# Hi-Hat_copy.net
KiCad netlist of a schematic drawn in EAGLE
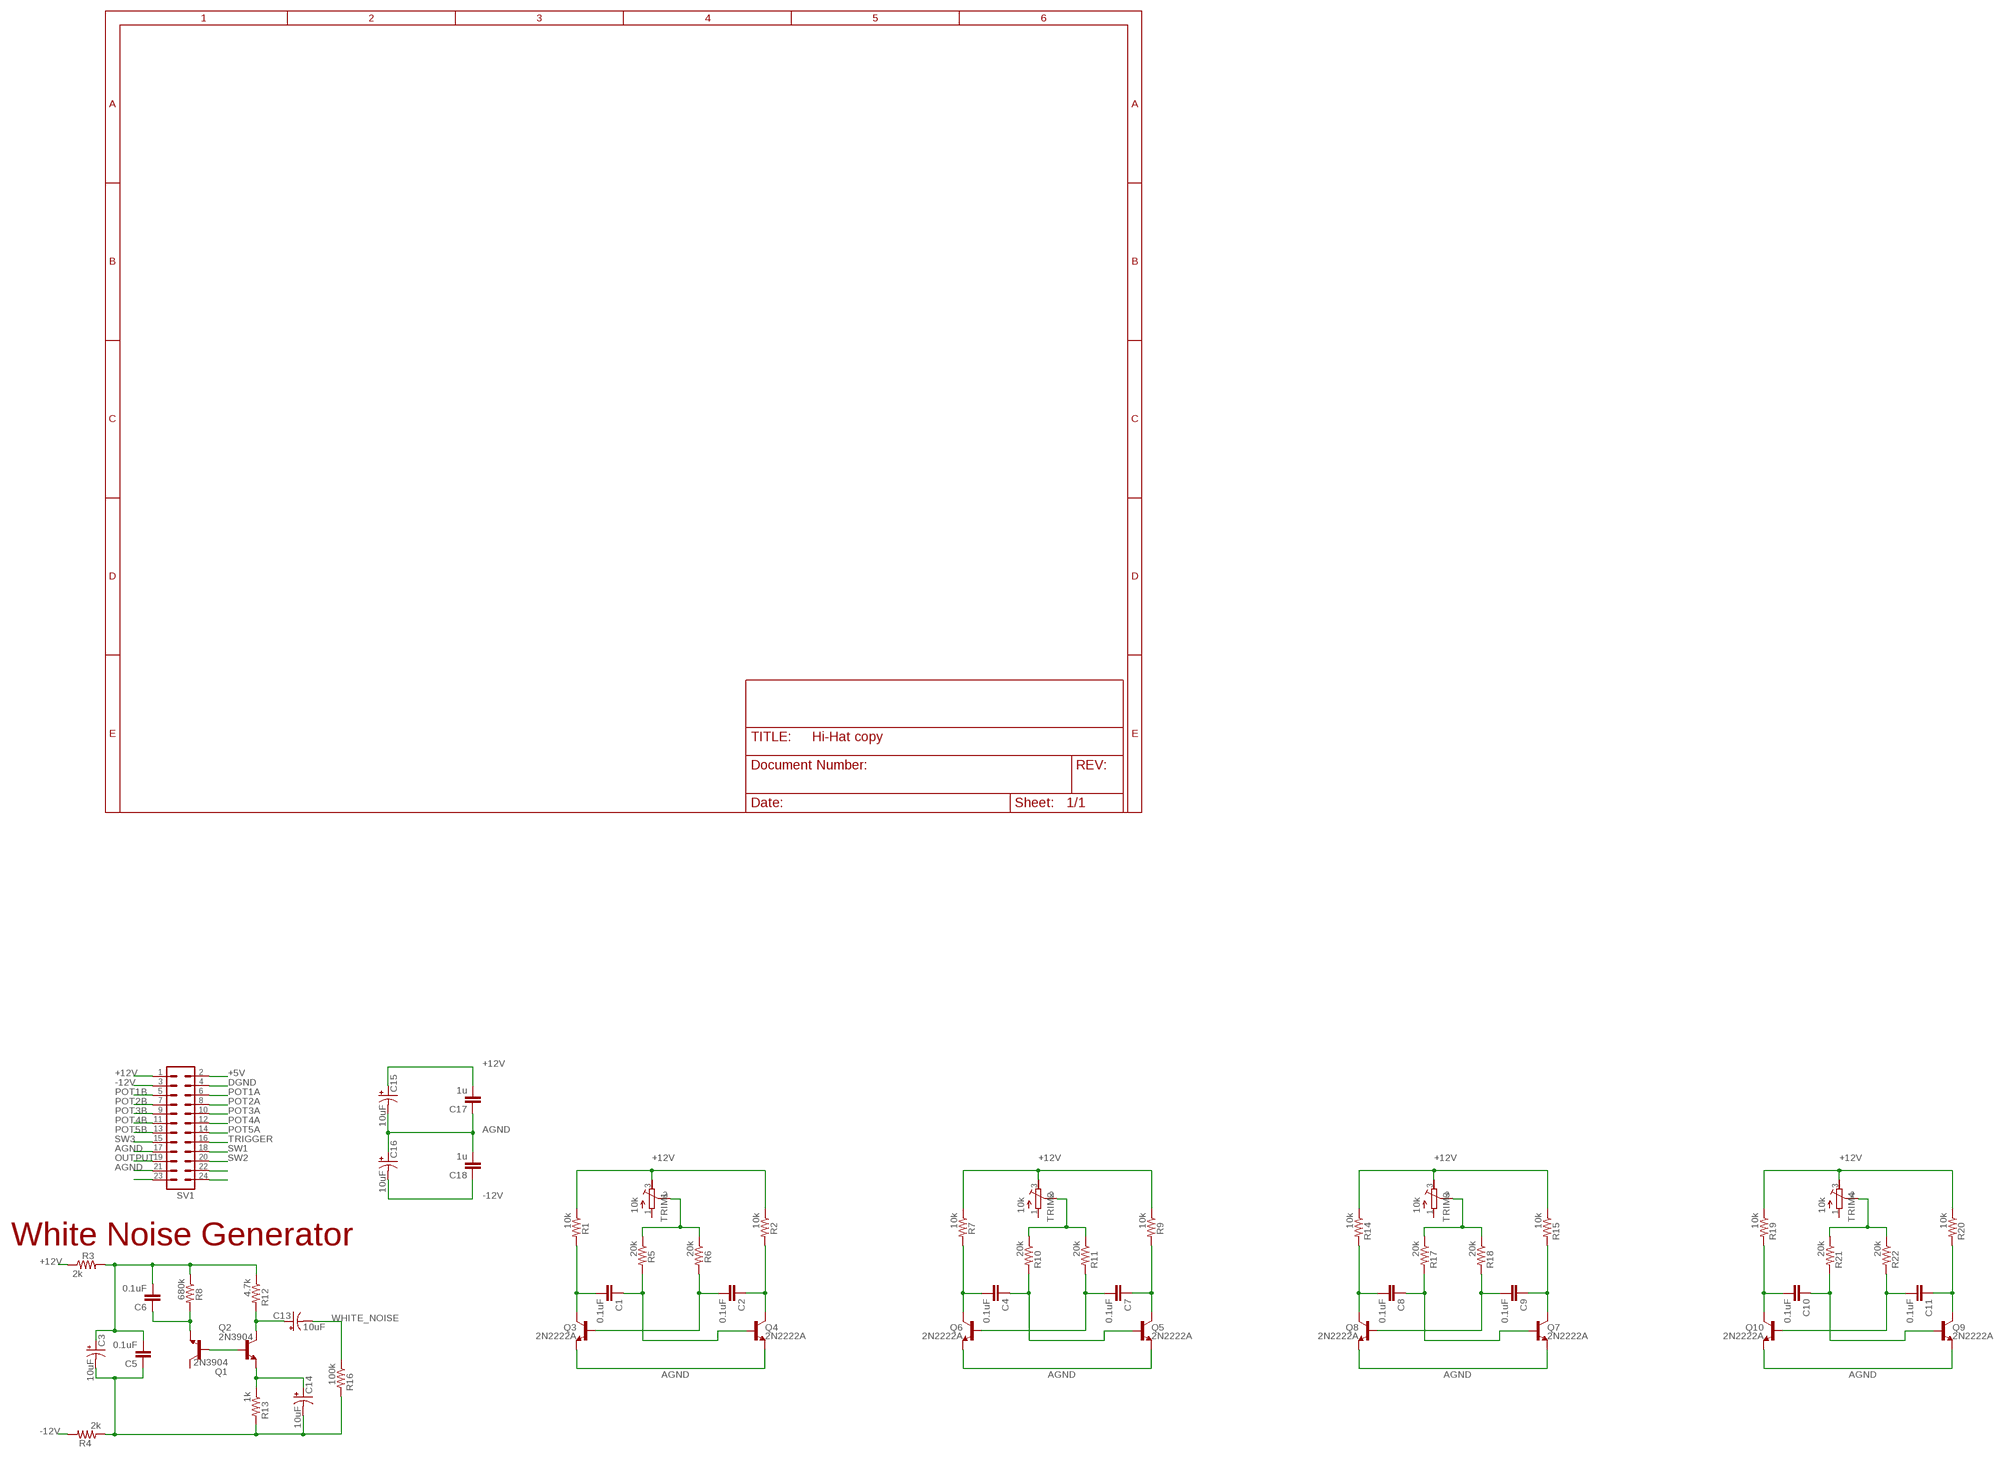
[diagram p0: schematic, sheet 1]

(export (version "E")
  (design (tool "Eeschema 10.0.6"))
  (components
    (comp (ref "C1")
      (value "0.1uF")
      (footprint "eagle-import:C050-024X044")
      (libsource (lib "eagle-import") (part "C-EU050-024X044"))
    )
    (comp (ref "C2")
      (value "0.1uF")
      (footprint "eagle-import:C050-024X044")
      (libsource (lib "eagle-import") (part "C-EU050-024X044"))
    )
    (comp (ref "C3")
      (value "10uF")
      (footprint "eagle-import:E2,5-6")
      (libsource (lib "eagle-import") (part "CPOL-USE2.5-6"))
    )
    (comp (ref "C4")
      (value "0.1uF")
      (footprint "eagle-import:C050-024X044")
      (libsource (lib "eagle-import") (part "C-EU050-024X044"))
    )
    (comp (ref "C5")
      (value "0.1uF")
      (footprint "eagle-import:C050-024X044")
      (libsource (lib "eagle-import") (part "C-EU050-024X044"))
    )
    (comp (ref "C6")
      (value "0.1uF")
      (footprint "eagle-import:C050-024X044")
      (libsource (lib "eagle-import") (part "C-EU050-024X044"))
    )
    (comp (ref "C7")
      (value "0.1uF")
      (footprint "eagle-import:C050-024X044")
      (libsource (lib "eagle-import") (part "C-EU050-024X044"))
    )
    (comp (ref "C8")
      (value "0.1uF")
      (footprint "eagle-import:C050-024X044")
      (libsource (lib "eagle-import") (part "C-EU050-024X044"))
    )
    (comp (ref "C9")
      (value "0.1uF")
      (footprint "eagle-import:C050-024X044")
      (libsource (lib "eagle-import") (part "C-EU050-024X044"))
    )
    (comp (ref "C10")
      (value "0.1uF")
      (footprint "eagle-import:C050-024X044")
      (libsource (lib "eagle-import") (part "C-EU050-024X044"))
    )
    (comp (ref "C11")
      (value "0.1uF")
      (footprint "eagle-import:C050-024X044")
      (libsource (lib "eagle-import") (part "C-EU050-024X044"))
    )
    (comp (ref "C13")
      (value "10uF")
      (footprint "eagle-import:E2,5-6")
      (libsource (lib "eagle-import") (part "CPOL-USE2.5-6"))
    )
    (comp (ref "C14")
      (value "10uF")
      (footprint "eagle-import:E2,5-6")
      (libsource (lib "eagle-import") (part "CPOL-USE2.5-6"))
    )
    (comp (ref "C15")
      (value "10uF")
      (footprint "eagle-import:E2,5-6")
      (libsource (lib "eagle-import") (part "CPOL-USE2.5-6"))
    )
    (comp (ref "C16")
      (value "10uF")
      (footprint "eagle-import:E2,5-6")
      (libsource (lib "eagle-import") (part "CPOL-USE2.5-6"))
    )
    (comp (ref "C17")
      (value "1u")
      (footprint "eagle-import:C050-024X044")
      (libsource (lib "eagle-import") (part "C-EU050-024X044"))
    )
    (comp (ref "C18")
      (value "1u")
      (footprint "eagle-import:C050-024X044")
      (libsource (lib "eagle-import") (part "C-EU050-024X044"))
    )
    (comp (ref "Q1")
      (value "2N3904")
      (footprint "eagle-import:TO92")
      (libsource (lib "eagle-import") (part "2N3904"))
    )
    (comp (ref "Q2")
      (value "2N3904")
      (footprint "eagle-import:TO92")
      (libsource (lib "eagle-import") (part "2N3904"))
    )
    (comp (ref "Q3")
      (value "2N2222A")
      (footprint "eagle-import:TO-92")
      (libsource (lib "eagle-import") (part "TRANS_NPN-P2N2222A"))
    )
    (comp (ref "Q4")
      (value "2N2222A")
      (footprint "eagle-import:TO-92")
      (libsource (lib "eagle-import") (part "TRANS_NPN-P2N2222A"))
    )
    (comp (ref "Q5")
      (value "2N2222A")
      (footprint "eagle-import:TO-92")
      (libsource (lib "eagle-import") (part "TRANS_NPN-P2N2222A"))
    )
    (comp (ref "Q6")
      (value "2N2222A")
      (footprint "eagle-import:TO-92")
      (libsource (lib "eagle-import") (part "TRANS_NPN-P2N2222A"))
    )
    (comp (ref "Q7")
      (value "2N2222A")
      (footprint "eagle-import:TO-92")
      (libsource (lib "eagle-import") (part "TRANS_NPN-P2N2222A"))
    )
    (comp (ref "Q8")
      (value "2N2222A")
      (footprint "eagle-import:TO-92")
      (libsource (lib "eagle-import") (part "TRANS_NPN-P2N2222A"))
    )
    (comp (ref "Q9")
      (value "2N2222A")
      (footprint "eagle-import:TO-92")
      (libsource (lib "eagle-import") (part "TRANS_NPN-P2N2222A"))
    )
    (comp (ref "Q10")
      (value "2N2222A")
      (footprint "eagle-import:TO-92")
      (libsource (lib "eagle-import") (part "TRANS_NPN-P2N2222A"))
    )
    (comp (ref "R1")
      (value "10k")
      (footprint "eagle-import:0207_10")
      (libsource (lib "eagle-import") (part "R-US_0207/10"))
    )
    (comp (ref "R2")
      (value "10k")
      (footprint "eagle-import:0207_10")
      (libsource (lib "eagle-import") (part "R-US_0207/10"))
    )
    (comp (ref "R3")
      (value "2k")
      (footprint "eagle-import:0207_10")
      (libsource (lib "eagle-import") (part "R-US_0207/10"))
    )
    (comp (ref "R4")
      (value "2k")
      (footprint "eagle-import:0207_10")
      (libsource (lib "eagle-import") (part "R-US_0207/10"))
    )
    (comp (ref "R5")
      (value "20k")
      (footprint "eagle-import:0207_10")
      (libsource (lib "eagle-import") (part "R-US_0207/10"))
    )
    (comp (ref "R6")
      (value "20k")
      (footprint "eagle-import:0207_10")
      (libsource (lib "eagle-import") (part "R-US_0207/10"))
    )
    (comp (ref "R7")
      (value "10k")
      (footprint "eagle-import:0207_10")
      (libsource (lib "eagle-import") (part "R-US_0207/10"))
    )
    (comp (ref "R8")
      (value "680k")
      (footprint "eagle-import:0207_10")
      (libsource (lib "eagle-import") (part "R-US_0207/10"))
    )
    (comp (ref "R9")
      (value "10k")
      (footprint "eagle-import:0207_10")
      (libsource (lib "eagle-import") (part "R-US_0207/10"))
    )
    (comp (ref "R10")
      (value "20k")
      (footprint "eagle-import:0207_10")
      (libsource (lib "eagle-import") (part "R-US_0207/10"))
    )
    (comp (ref "R11")
      (value "20k")
      (footprint "eagle-import:0207_10")
      (libsource (lib "eagle-import") (part "R-US_0207/10"))
    )
    (comp (ref "R12")
      (value "4.7k")
      (footprint "eagle-import:0207_10")
      (libsource (lib "eagle-import") (part "R-US_0207/10"))
    )
    (comp (ref "R13")
      (value "1k")
      (footprint "eagle-import:0207_10")
      (libsource (lib "eagle-import") (part "R-US_0207/10"))
    )
    (comp (ref "R14")
      (value "10k")
      (footprint "eagle-import:0207_10")
      (libsource (lib "eagle-import") (part "R-US_0207/10"))
    )
    (comp (ref "R15")
      (value "10k")
      (footprint "eagle-import:0207_10")
      (libsource (lib "eagle-import") (part "R-US_0207/10"))
    )
    (comp (ref "R16")
      (value "100k")
      (footprint "eagle-import:0207_10")
      (libsource (lib "eagle-import") (part "R-US_0207/10"))
    )
    (comp (ref "R17")
      (value "20k")
      (footprint "eagle-import:0207_10")
      (libsource (lib "eagle-import") (part "R-US_0207/10"))
    )
    (comp (ref "R18")
      (value "20k")
      (footprint "eagle-import:0207_10")
      (libsource (lib "eagle-import") (part "R-US_0207/10"))
    )
    (comp (ref "R19")
      (value "10k")
      (footprint "eagle-import:0207_10")
      (libsource (lib "eagle-import") (part "R-US_0207/10"))
    )
    (comp (ref "R20")
      (value "10k")
      (footprint "eagle-import:0207_10")
      (libsource (lib "eagle-import") (part "R-US_0207/10"))
    )
    (comp (ref "R21")
      (value "20k")
      (footprint "eagle-import:0207_10")
      (libsource (lib "eagle-import") (part "R-US_0207/10"))
    )
    (comp (ref "R22")
      (value "20k")
      (footprint "eagle-import:0207_10")
      (libsource (lib "eagle-import") (part "R-US_0207/10"))
    )
    (comp (ref "SV1")
      (value "MA12-2")
      (footprint "eagle-import:MA12-2")
      (libsource (lib "eagle-import") (part "MA12-2"))
    )
    (comp (ref "TRIM1")
      (value "10k")
      (footprint "eagle-import:RTRIM64W")
      (libsource (lib "eagle-import") (part "R-TRIMM64W"))
    )
    (comp (ref "TRIM2")
      (value "10k")
      (footprint "eagle-import:RTRIM64W")
      (libsource (lib "eagle-import") (part "R-TRIMM64W"))
    )
    (comp (ref "TRIM3")
      (value "10k")
      (footprint "eagle-import:RTRIM64W")
      (libsource (lib "eagle-import") (part "R-TRIMM64W"))
    )
    (comp (ref "TRIM4")
      (value "10k")
      (footprint "eagle-import:RTRIM64W")
      (libsource (lib "eagle-import") (part "R-TRIMM64W"))
    )
  )
  (nets
    (net (code "1") (name "/+5V") (class "Default")
      (node (ref "SV1") (pin "2") (pinfunction "2_2") (pintype "passive"))
    )
    (net (code "2") (name "/+12V") (class "Default")
      (node (ref "C15") (pin "+") (pinfunction "+_+") (pintype "passive"))
      (node (ref "C17") (pin "2") (pinfunction "2_2") (pintype "passive"))
      (node (ref "R1") (pin "1") (pinfunction "1_1") (pintype "passive"))
      (node (ref "R14") (pin "1") (pinfunction "1_1") (pintype "passive"))
      (node (ref "R15") (pin "1") (pinfunction "1_1") (pintype "passive"))
      (node (ref "R19") (pin "1") (pinfunction "1_1") (pintype "passive"))
      (node (ref "R2") (pin "1") (pinfunction "1_1") (pintype "passive"))
      (node (ref "R20") (pin "1") (pinfunction "1_1") (pintype "passive"))
      (node (ref "R3") (pin "1") (pinfunction "1_1") (pintype "passive"))
      (node (ref "R7") (pin "1") (pinfunction "1_1") (pintype "passive"))
      (node (ref "R9") (pin "1") (pinfunction "1_1") (pintype "passive"))
      (node (ref "SV1") (pin "1") (pinfunction "1_1") (pintype "passive"))
      (node (ref "TRIM1") (pin "3") (pinfunction "E_3") (pintype "passive"))
      (node (ref "TRIM2") (pin "3") (pinfunction "E_3") (pintype "passive"))
      (node (ref "TRIM3") (pin "3") (pinfunction "E_3") (pintype "passive"))
      (node (ref "TRIM4") (pin "3") (pinfunction "E_3") (pintype "passive"))
    )
    (net (code "3") (name "/-12V") (class "Default")
      (node (ref "C16") (pin "-") (pinfunction "-_-") (pintype "passive"))
      (node (ref "C18") (pin "1") (pinfunction "1_1") (pintype "passive"))
      (node (ref "R4") (pin "2") (pinfunction "2_2") (pintype "passive"))
      (node (ref "SV1") (pin "3") (pinfunction "3_3") (pintype "passive"))
    )
    (net (code "4") (name "/AGND") (class "Default")
      (node (ref "C15") (pin "-") (pinfunction "-_-") (pintype "passive"))
      (node (ref "C16") (pin "+") (pinfunction "+_+") (pintype "passive"))
      (node (ref "C17") (pin "1") (pinfunction "1_1") (pintype "passive"))
      (node (ref "C18") (pin "2") (pinfunction "2_2") (pintype "passive"))
      (node (ref "Q10") (pin "3") (pinfunction "E_3") (pintype "passive"))
      (node (ref "Q3") (pin "3") (pinfunction "E_3") (pintype "passive"))
      (node (ref "Q4") (pin "3") (pinfunction "E_3") (pintype "passive"))
      (node (ref "Q5") (pin "3") (pinfunction "E_3") (pintype "passive"))
      (node (ref "Q6") (pin "3") (pinfunction "E_3") (pintype "passive"))
      (node (ref "Q7") (pin "3") (pinfunction "E_3") (pintype "passive"))
      (node (ref "Q8") (pin "3") (pinfunction "E_3") (pintype "passive"))
      (node (ref "Q9") (pin "3") (pinfunction "E_3") (pintype "passive"))
      (node (ref "SV1") (pin "17") (pinfunction "17_17") (pintype "passive"))
      (node (ref "SV1") (pin "21") (pinfunction "21_21") (pintype "passive"))
    )
    (net (code "5") (name "/DGND") (class "Default")
      (node (ref "SV1") (pin "4") (pinfunction "4_4") (pintype "passive"))
    )
    (net (code "6") (name "/OUTPUT") (class "Default")
      (node (ref "SV1") (pin "19") (pinfunction "19_19") (pintype "passive"))
    )
    (net (code "7") (name "/POT1A") (class "Default")
      (node (ref "SV1") (pin "6") (pinfunction "6_6") (pintype "passive"))
    )
    (net (code "8") (name "/POT1B") (class "Default")
      (node (ref "SV1") (pin "5") (pinfunction "5_5") (pintype "passive"))
    )
    (net (code "9") (name "/POT2A") (class "Default")
      (node (ref "SV1") (pin "8") (pinfunction "8_8") (pintype "passive"))
    )
    (net (code "10") (name "/POT2B") (class "Default")
      (node (ref "SV1") (pin "7") (pinfunction "7_7") (pintype "passive"))
    )
    (net (code "11") (name "/POT3A") (class "Default")
      (node (ref "SV1") (pin "10") (pinfunction "10_10") (pintype "passive"))
    )
    (net (code "12") (name "/POT3B") (class "Default")
      (node (ref "SV1") (pin "9") (pinfunction "9_9") (pintype "passive"))
    )
    (net (code "13") (name "/POT4A") (class "Default")
      (node (ref "SV1") (pin "12") (pinfunction "12_12") (pintype "passive"))
    )
    (net (code "14") (name "/POT4B") (class "Default")
      (node (ref "SV1") (pin "11") (pinfunction "11_11") (pintype "passive"))
    )
    (net (code "15") (name "/POT5A") (class "Default")
      (node (ref "SV1") (pin "14") (pinfunction "14_14") (pintype "passive"))
    )
    (net (code "16") (name "/POT5B") (class "Default")
      (node (ref "SV1") (pin "13") (pinfunction "13_13") (pintype "passive"))
    )
    (net (code "17") (name "/SW1") (class "Default")
      (node (ref "SV1") (pin "18") (pinfunction "18_18") (pintype "passive"))
    )
    (net (code "18") (name "/SW2") (class "Default")
      (node (ref "SV1") (pin "20") (pinfunction "20_20") (pintype "passive"))
    )
    (net (code "19") (name "/SW3") (class "Default")
      (node (ref "SV1") (pin "15") (pinfunction "15_15") (pintype "passive"))
    )
    (net (code "20") (name "/TRIGGER") (class "Default")
      (node (ref "SV1") (pin "16") (pinfunction "16_16") (pintype "passive"))
    )
    (net (code "21") (name "/WHITE_NOISE") (class "Default")
      (node (ref "C13") (pin "-") (pinfunction "-_-") (pintype "passive"))
      (node (ref "R16") (pin "1") (pinfunction "1_1") (pintype "passive"))
    )
    (net (code "22") (name "Net-(C3-Pad+)") (class "Default")
      (node (ref "C3") (pin "+") (pinfunction "+_+") (pintype "passive"))
      (node (ref "C5") (pin "2") (pinfunction "2_2") (pintype "passive"))
      (node (ref "C6") (pin "2") (pinfunction "2_2") (pintype "passive"))
      (node (ref "R12") (pin "1") (pinfunction "1_1") (pintype "passive"))
      (node (ref "R3") (pin "2") (pinfunction "2_2") (pintype "passive"))
      (node (ref "R8") (pin "1") (pinfunction "1_1") (pintype "passive"))
    )
    (net (code "23") (name "Net-(C14-Pad-)") (class "Default")
      (node (ref "C14") (pin "-") (pinfunction "-_-") (pintype "passive"))
      (node (ref "C3") (pin "-") (pinfunction "-_-") (pintype "passive"))
      (node (ref "C5") (pin "1") (pinfunction "1_1") (pintype "passive"))
      (node (ref "R13") (pin "2") (pinfunction "2_2") (pintype "passive"))
      (node (ref "R16") (pin "2") (pinfunction "2_2") (pintype "passive"))
      (node (ref "R4") (pin "1") (pinfunction "1_1") (pintype "passive"))
    )
    (net (code "24") (name "Net-(Q1-B)") (class "Default")
      (node (ref "Q1") (pin "2") (pinfunction "B_2") (pintype "passive"))
      (node (ref "Q2") (pin "2") (pinfunction "B_2") (pintype "passive"))
    )
    (net (code "25") (name "Net-(Q1-E)") (class "Default")
      (node (ref "C6") (pin "1") (pinfunction "1_1") (pintype "passive"))
      (node (ref "Q1") (pin "3") (pinfunction "E_3") (pintype "passive"))
      (node (ref "R8") (pin "2") (pinfunction "2_2") (pintype "passive"))
    )
    (net (code "26") (name "Net-(Q2-C)") (class "Default")
      (node (ref "C13") (pin "+") (pinfunction "+_+") (pintype "passive"))
      (node (ref "Q2") (pin "1") (pinfunction "C_1") (pintype "passive"))
      (node (ref "R12") (pin "2") (pinfunction "2_2") (pintype "passive"))
    )
    (net (code "27") (name "Net-(Q2-E)") (class "Default")
      (node (ref "C14") (pin "+") (pinfunction "+_+") (pintype "passive"))
      (node (ref "Q2") (pin "3") (pinfunction "E_3") (pintype "passive"))
      (node (ref "R13") (pin "1") (pinfunction "1_1") (pintype "passive"))
    )
    (net (code "28") (name "Net-(Q3-B)") (class "Default")
      (node (ref "C2") (pin "2") (pinfunction "2_2") (pintype "passive"))
      (node (ref "Q3") (pin "2") (pinfunction "B_2") (pintype "passive"))
      (node (ref "R6") (pin "2") (pinfunction "2_2") (pintype "passive"))
    )
    (net (code "29") (name "Net-(Q3-C)") (class "Default")
      (node (ref "C1") (pin "2") (pinfunction "2_2") (pintype "passive"))
      (node (ref "Q3") (pin "1") (pinfunction "C_1") (pintype "passive"))
      (node (ref "R1") (pin "2") (pinfunction "2_2") (pintype "passive"))
    )
    (net (code "30") (name "Net-(Q4-B)") (class "Default")
      (node (ref "C1") (pin "1") (pinfunction "1_1") (pintype "passive"))
      (node (ref "Q4") (pin "2") (pinfunction "B_2") (pintype "passive"))
      (node (ref "R5") (pin "2") (pinfunction "2_2") (pintype "passive"))
    )
    (net (code "31") (name "Net-(Q4-C)") (class "Default")
      (node (ref "C2") (pin "1") (pinfunction "1_1") (pintype "passive"))
      (node (ref "Q4") (pin "1") (pinfunction "C_1") (pintype "passive"))
      (node (ref "R2") (pin "2") (pinfunction "2_2") (pintype "passive"))
    )
    (net (code "32") (name "Net-(Q5-B)") (class "Default")
      (node (ref "C4") (pin "1") (pinfunction "1_1") (pintype "passive"))
      (node (ref "Q5") (pin "2") (pinfunction "B_2") (pintype "passive"))
      (node (ref "R10") (pin "2") (pinfunction "2_2") (pintype "passive"))
    )
    (net (code "33") (name "Net-(Q5-C)") (class "Default")
      (node (ref "C7") (pin "1") (pinfunction "1_1") (pintype "passive"))
      (node (ref "Q5") (pin "1") (pinfunction "C_1") (pintype "passive"))
      (node (ref "R9") (pin "2") (pinfunction "2_2") (pintype "passive"))
    )
    (net (code "34") (name "Net-(Q6-B)") (class "Default")
      (node (ref "C7") (pin "2") (pinfunction "2_2") (pintype "passive"))
      (node (ref "Q6") (pin "2") (pinfunction "B_2") (pintype "passive"))
      (node (ref "R11") (pin "2") (pinfunction "2_2") (pintype "passive"))
    )
    (net (code "35") (name "Net-(Q6-C)") (class "Default")
      (node (ref "C4") (pin "2") (pinfunction "2_2") (pintype "passive"))
      (node (ref "Q6") (pin "1") (pinfunction "C_1") (pintype "passive"))
      (node (ref "R7") (pin "2") (pinfunction "2_2") (pintype "passive"))
    )
    (net (code "36") (name "Net-(Q7-B)") (class "Default")
      (node (ref "C8") (pin "1") (pinfunction "1_1") (pintype "passive"))
      (node (ref "Q7") (pin "2") (pinfunction "B_2") (pintype "passive"))
      (node (ref "R17") (pin "2") (pinfunction "2_2") (pintype "passive"))
    )
    (net (code "37") (name "Net-(Q7-C)") (class "Default")
      (node (ref "C9") (pin "1") (pinfunction "1_1") (pintype "passive"))
      (node (ref "Q7") (pin "1") (pinfunction "C_1") (pintype "passive"))
      (node (ref "R15") (pin "2") (pinfunction "2_2") (pintype "passive"))
    )
    (net (code "38") (name "Net-(Q8-B)") (class "Default")
      (node (ref "C9") (pin "2") (pinfunction "2_2") (pintype "passive"))
      (node (ref "Q8") (pin "2") (pinfunction "B_2") (pintype "passive"))
      (node (ref "R18") (pin "2") (pinfunction "2_2") (pintype "passive"))
    )
    (net (code "39") (name "Net-(Q8-C)") (class "Default")
      (node (ref "C8") (pin "2") (pinfunction "2_2") (pintype "passive"))
      (node (ref "Q8") (pin "1") (pinfunction "C_1") (pintype "passive"))
      (node (ref "R14") (pin "2") (pinfunction "2_2") (pintype "passive"))
    )
    (net (code "40") (name "Net-(Q9-B)") (class "Default")
      (node (ref "C10") (pin "1") (pinfunction "1_1") (pintype "passive"))
      (node (ref "Q9") (pin "2") (pinfunction "B_2") (pintype "passive"))
      (node (ref "R21") (pin "2") (pinfunction "2_2") (pintype "passive"))
    )
    (net (code "41") (name "Net-(Q9-C)") (class "Default")
      (node (ref "C11") (pin "1") (pinfunction "1_1") (pintype "passive"))
      (node (ref "Q9") (pin "1") (pinfunction "C_1") (pintype "passive"))
      (node (ref "R20") (pin "2") (pinfunction "2_2") (pintype "passive"))
    )
    (net (code "42") (name "Net-(Q10-B)") (class "Default")
      (node (ref "C11") (pin "2") (pinfunction "2_2") (pintype "passive"))
      (node (ref "Q10") (pin "2") (pinfunction "B_2") (pintype "passive"))
      (node (ref "R22") (pin "2") (pinfunction "2_2") (pintype "passive"))
    )
    (net (code "43") (name "Net-(Q10-C)") (class "Default")
      (node (ref "C10") (pin "2") (pinfunction "2_2") (pintype "passive"))
      (node (ref "Q10") (pin "1") (pinfunction "C_1") (pintype "passive"))
      (node (ref "R19") (pin "2") (pinfunction "2_2") (pintype "passive"))
    )
    (net (code "44") (name "Net-(TRIM1-S)") (class "Default")
      (node (ref "R5") (pin "1") (pinfunction "1_1") (pintype "passive"))
      (node (ref "R6") (pin "1") (pinfunction "1_1") (pintype "passive"))
      (node (ref "TRIM1") (pin "2") (pinfunction "S_2") (pintype "passive"))
    )
    (net (code "45") (name "Net-(TRIM2-S)") (class "Default")
      (node (ref "R10") (pin "1") (pinfunction "1_1") (pintype "passive"))
      (node (ref "R11") (pin "1") (pinfunction "1_1") (pintype "passive"))
      (node (ref "TRIM2") (pin "2") (pinfunction "S_2") (pintype "passive"))
    )
    (net (code "46") (name "Net-(TRIM3-S)") (class "Default")
      (node (ref "R17") (pin "1") (pinfunction "1_1") (pintype "passive"))
      (node (ref "R18") (pin "1") (pinfunction "1_1") (pintype "passive"))
      (node (ref "TRIM3") (pin "2") (pinfunction "S_2") (pintype "passive"))
    )
    (net (code "47") (name "Net-(TRIM4-S)") (class "Default")
      (node (ref "R21") (pin "1") (pinfunction "1_1") (pintype "passive"))
      (node (ref "R22") (pin "1") (pinfunction "1_1") (pintype "passive"))
      (node (ref "TRIM4") (pin "2") (pinfunction "S_2") (pintype "passive"))
    )
    (net (code "48") (name "unconnected-(Q1-C-Pad1)") (class "Default")
      (node (ref "Q1") (pin "1") (pinfunction "C_1") (pintype "passive"))
    )
    (net (code "49") (name "unconnected-(SV1-Pad22)") (class "Default")
      (node (ref "SV1") (pin "22") (pinfunction "22_22") (pintype "passive"))
    )
    (net (code "50") (name "unconnected-(SV1-Pad23)") (class "Default")
      (node (ref "SV1") (pin "23") (pinfunction "23_23") (pintype "passive"))
    )
    (net (code "51") (name "unconnected-(SV1-Pad24)") (class "Default")
      (node (ref "SV1") (pin "24") (pinfunction "24_24") (pintype "passive"))
    )
    (net (code "52") (name "unconnected-(TRIM1-A-Pad1)") (class "Default")
      (node (ref "TRIM1") (pin "1") (pinfunction "A_1") (pintype "passive"))
    )
    (net (code "53") (name "unconnected-(TRIM2-A-Pad1)") (class "Default")
      (node (ref "TRIM2") (pin "1") (pinfunction "A_1") (pintype "passive"))
    )
    (net (code "54") (name "unconnected-(TRIM3-A-Pad1)") (class "Default")
      (node (ref "TRIM3") (pin "1") (pinfunction "A_1") (pintype "passive"))
    )
    (net (code "55") (name "unconnected-(TRIM4-A-Pad1)") (class "Default")
      (node (ref "TRIM4") (pin "1") (pinfunction "A_1") (pintype "passive"))
    )
  )
)
